# Battery_Manager.net
KiCad netlist of a schematic drawn in Altium Designer
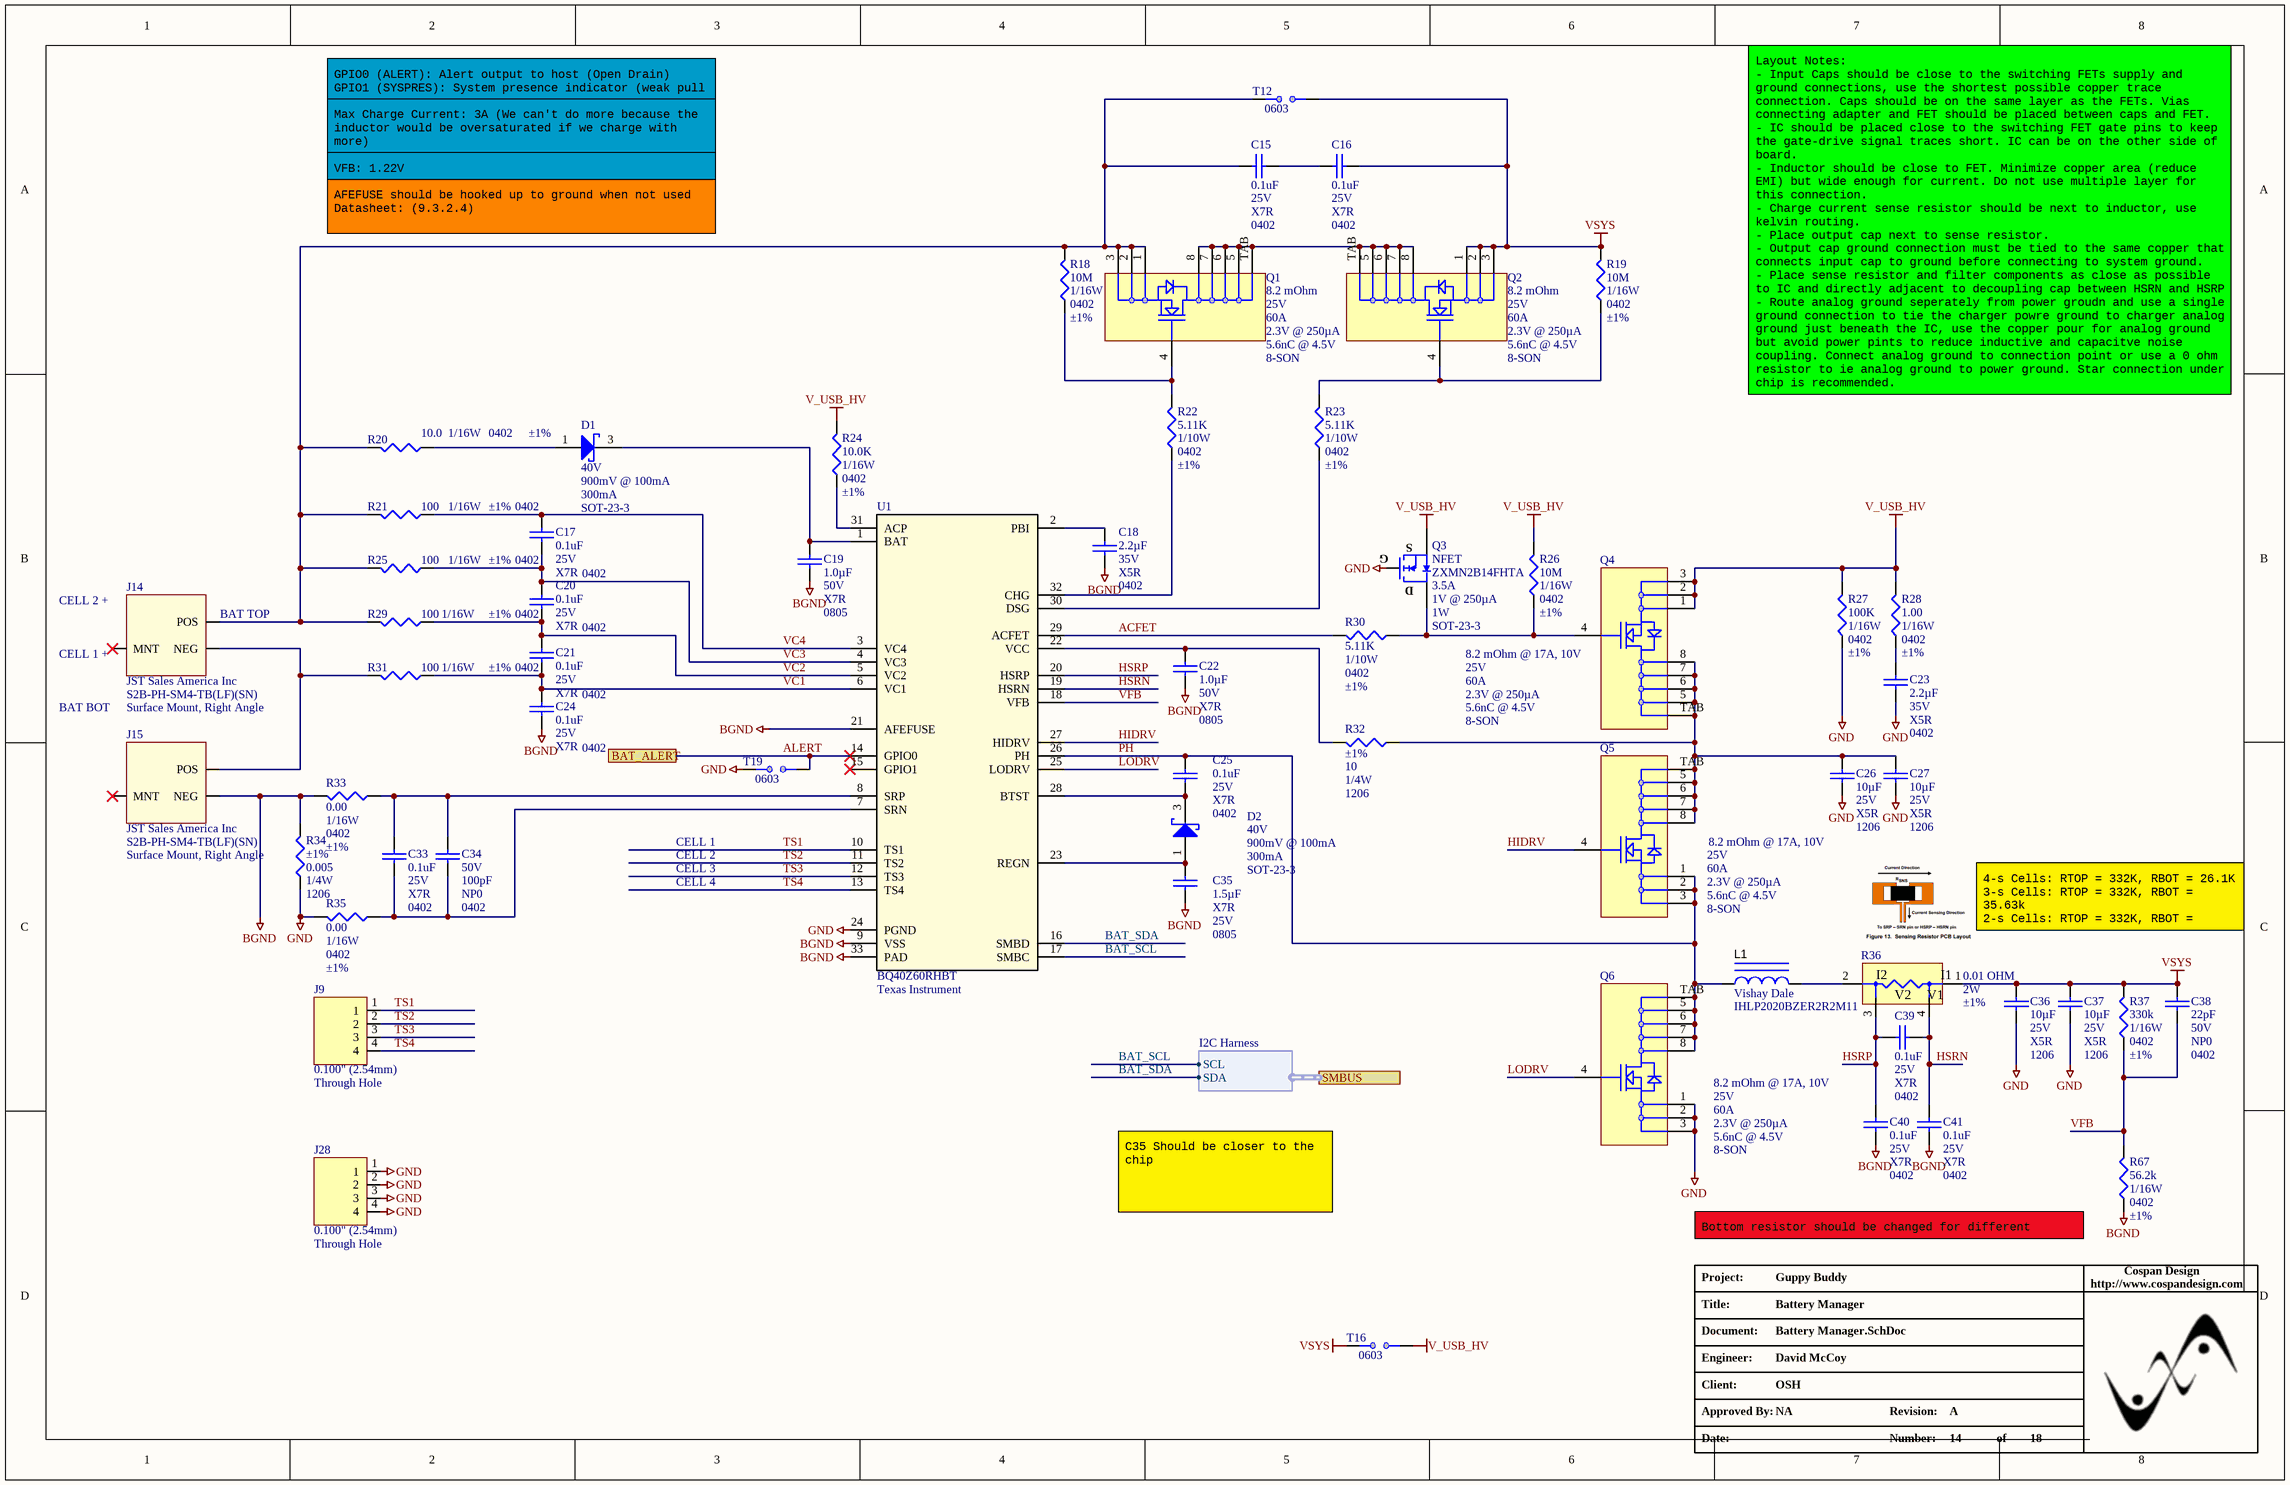
[diagram p0: Battery Manager.SchDoc]

(export (version "E")
  (design (tool "Eeschema 10.0.6"))
  (components
    (comp (ref "C15")
      (value "C_0402_0.1UF_25V")
      (footprint "C_0402")
      (description "CAP CER 0.1UF 25V X6S 0402")
      (fields
        (field (name "TOLERANCE") "10%")
        (field (name "CAPACITANCE") "0.1uF")
        (field (name "VOLTAGE - RATED") "25V")
        (field (name "TEMPERATURE COEFFICIENT") "X7R")
        (field (name "PACKAGE / CASE") "0402")
      )
      (libsource (lib "Cospan Design") (part "C_0402_0.1UF_25V"))
    )
    (comp (ref "C16")
      (value "C_0402_0.1UF_25V")
      (footprint "C_0402")
      (description "CAP CER 0.1UF 25V X6S 0402")
      (fields
        (field (name "TOLERANCE") "10%")
        (field (name "CAPACITANCE") "0.1uF")
        (field (name "VOLTAGE - RATED") "25V")
        (field (name "TEMPERATURE COEFFICIENT") "X7R")
        (field (name "PACKAGE / CASE") "0402")
      )
      (libsource (lib "Cospan Design") (part "C_0402_0.1UF_25V"))
    )
    (comp (ref "C17")
      (value "C_0402_0.1UF_25V")
      (footprint "C_0402")
      (description "CAP CER 0.1UF 25V X6S 0402")
      (fields
        (field (name "TOLERANCE") "10%")
        (field (name "CAPACITANCE") "0.1uF")
        (field (name "VOLTAGE - RATED") "25V")
        (field (name "TEMPERATURE COEFFICIENT") "X7R")
        (field (name "PACKAGE / CASE") "0402")
      )
      (libsource (lib "Cospan Design") (part "C_0402_0.1UF_25V"))
    )
    (comp (ref "C18")
      (value "C_0402_2.2uF_35V")
      (footprint "C_0402")
      (description "CAP CER 2.2UF 35V 20% X5R 0402")
      (fields
        (field (name "MANUFACTURER") "TDK Corporation")
        (field (name "MANUFACTURER PART NUMBER") "C1005X5R1V225K050BC")
        (field (name "CAPACITANCE") "2.2µF")
        (field (name "VOLTAGE - RATED") "35V")
        (field (name "TEMPERATURE COEFFICIENT") "X5R")
        (field (name "PACKAGE / CASE") "0402")
      )
      (libsource (lib "Main LibraryX") (part "C_0402_2.2uF_35V"))
    )
    (comp (ref "C19")
      (value "1.0uF")
      (footprint "C_ERA-0805")
      (description "CAP CER 1UF 50V X7R 0805")
      (fields
        (field (name "TOLERANCE") "10%")
        (field (name "CAPACITANCE") "1.0µF")
        (field (name "VOLTAGE - RATED") "50V")
        (field (name "TEMPERATURE COEFFICIENT") "X7R")
        (field (name "PACKAGE / CASE") "0805")
        (field (name "VOLTAGE") "50V")
      )
      (libsource (lib "Main LibraryX") (part "C_0805_1.0uF_50V"))
    )
    (comp (ref "C20")
      (value "C_0402_0.1UF_25V")
      (footprint "C_0402")
      (description "CAP CER 0.1UF 25V X6S 0402")
      (fields
        (field (name "TOLERANCE") "10%")
        (field (name "CAPACITANCE") "0.1uF")
        (field (name "VOLTAGE - RATED") "25V")
        (field (name "TEMPERATURE COEFFICIENT") "X7R")
        (field (name "PACKAGE / CASE") "0402")
      )
      (libsource (lib "Cospan Design") (part "C_0402_0.1UF_25V"))
    )
    (comp (ref "C21")
      (value "C_0402_0.1UF_25V")
      (footprint "C_0402")
      (description "CAP CER 0.1UF 25V X6S 0402")
      (fields
        (field (name "TOLERANCE") "10%")
        (field (name "CAPACITANCE") "0.1uF")
        (field (name "VOLTAGE - RATED") "25V")
        (field (name "TEMPERATURE COEFFICIENT") "X7R")
        (field (name "PACKAGE / CASE") "0402")
      )
      (libsource (lib "Cospan Design") (part "C_0402_0.1UF_25V"))
    )
    (comp (ref "C22")
      (value "1.0uF")
      (footprint "C_ERA-0805")
      (description "CAP CER 1UF 50V X7R 0805")
      (fields
        (field (name "TOLERANCE") "10%")
        (field (name "CAPACITANCE") "1.0µF")
        (field (name "VOLTAGE - RATED") "50V")
        (field (name "TEMPERATURE COEFFICIENT") "X7R")
        (field (name "PACKAGE / CASE") "0805")
        (field (name "VOLTAGE") "50V")
      )
      (libsource (lib "Main LibraryX") (part "C_0805_1.0uF_50V"))
    )
    (comp (ref "C23")
      (value "C_0402_2.2uF_35V")
      (footprint "C_0402")
      (description "CAP CER 2.2UF 35V 20% X5R 0402")
      (fields
        (field (name "MANUFACTURER") "TDK Corporation")
        (field (name "MANUFACTURER PART NUMBER") "C1005X5R1V225K050BC")
        (field (name "CAPACITANCE") "2.2µF")
        (field (name "VOLTAGE - RATED") "35V")
        (field (name "TEMPERATURE COEFFICIENT") "X5R")
        (field (name "PACKAGE / CASE") "0402")
      )
      (libsource (lib "Main LibraryX") (part "C_0402_2.2uF_35V"))
    )
    (comp (ref "C24")
      (value "C_0402_0.1UF_25V")
      (footprint "C_0402")
      (description "CAP CER 0.1UF 25V X6S 0402")
      (fields
        (field (name "TOLERANCE") "10%")
        (field (name "CAPACITANCE") "0.1uF")
        (field (name "VOLTAGE - RATED") "25V")
        (field (name "TEMPERATURE COEFFICIENT") "X7R")
        (field (name "PACKAGE / CASE") "0402")
      )
      (libsource (lib "Cospan Design") (part "C_0402_0.1UF_25V"))
    )
    (comp (ref "C25")
      (value "C_0402_0.1UF_25V")
      (footprint "C_0402")
      (description "CAP CER 0.1UF 25V X6S 0402")
      (fields
        (field (name "TOLERANCE") "10%")
        (field (name "CAPACITANCE") "0.1uF")
        (field (name "VOLTAGE - RATED") "25V")
        (field (name "TEMPERATURE COEFFICIENT") "X7R")
        (field (name "PACKAGE / CASE") "0402")
      )
      (libsource (lib "Cospan Design") (part "C_0402_0.1UF_25V"))
    )
    (comp (ref "C26")
      (value "10µF")
      (footprint "CAP-1206")
      (description "CAP CER 10UF 25V X5R 1206")
      (fields
        (field (name "TOLERANCE") "10%")
        (field (name "CAPACITANCE") "10µF")
        (field (name "VOLTAGE - RATED") "25V")
        (field (name "TEMPERATURE COEFFICIENT") "X5R")
        (field (name "PACKAGE / CASE") "1206")
        (field (name "VOLTAGE") "25V")
      )
      (libsource (lib "Main LibraryX") (part "C_1206_10UF_25V"))
    )
    (comp (ref "C27")
      (value "10µF")
      (footprint "CAP-1206")
      (description "CAP CER 10UF 25V X5R 1206")
      (fields
        (field (name "TOLERANCE") "10%")
        (field (name "CAPACITANCE") "10µF")
        (field (name "VOLTAGE - RATED") "25V")
        (field (name "TEMPERATURE COEFFICIENT") "X5R")
        (field (name "PACKAGE / CASE") "1206")
        (field (name "VOLTAGE") "25V")
      )
      (libsource (lib "Main LibraryX") (part "C_1206_10UF_25V"))
    )
    (comp (ref "C33")
      (value "C_0402_0.1UF_25V")
      (footprint "C_0402")
      (description "CAP CER 0.1UF 25V X6S 0402")
      (fields
        (field (name "TOLERANCE") "10%")
        (field (name "CAPACITANCE") "0.1uF")
        (field (name "VOLTAGE - RATED") "25V")
        (field (name "TEMPERATURE COEFFICIENT") "X7R")
        (field (name "PACKAGE / CASE") "0402")
      )
      (libsource (lib "Cospan Design") (part "C_0402_0.1UF_25V"))
    )
    (comp (ref "C34")
      (value "100pF")
      (footprint "C_0402")
      (description "CAP CER 100PF 50V 5% C0G 0402")
      (fields
        (field (name "MANUFACTURER") "Murata Electronics North America")
        (field (name "MANUFACTURER PART NUMBER") "GRM1555C1H101JA01D")
        (field (name "VOLTAGE - RATED") "50V")
        (field (name "CAPACITANCE") "100pF")
        (field (name "TEMPERATURE COEFFICIENT") "NP0")
        (field (name "PACKAGE / CASE") "0402")
      )
      (libsource (lib "Main LibraryX") (part "C_0402_100PF"))
    )
    (comp (ref "C35")
      (value "C_0805_1.5uF_25V")
      (footprint "C_ERA-0805")
      (description "1.5µF ±10% 25V Ceramic Capacitor X7R 0805 (2012 Metric)")
      (fields
        (field (name "MANUFACTURER") "Murata Electronics North America")
        (field (name "MANUFACTURER PART NUMBER") "GRM21BR71E155KA88L")
        (field (name "CAPACITANCE") "1.5µF")
        (field (name "VOLTAGE - RATED") "X7R")
        (field (name "TEMPERATURE COEFFICIENT") "25V")
        (field (name "PACKAGE / CASE") "0805")
      )
      (libsource (lib "Cospan Design") (part "C_0805_1.5uF_25V"))
    )
    (comp (ref "C36")
      (value "10µF")
      (footprint "CAP-1206")
      (description "CAP CER 10UF 25V X5R 1206")
      (fields
        (field (name "TOLERANCE") "10%")
        (field (name "CAPACITANCE") "10µF")
        (field (name "VOLTAGE - RATED") "25V")
        (field (name "TEMPERATURE COEFFICIENT") "X5R")
        (field (name "PACKAGE / CASE") "1206")
        (field (name "VOLTAGE") "25V")
      )
      (libsource (lib "Main LibraryX") (part "C_1206_10UF_25V"))
    )
    (comp (ref "C37")
      (value "10µF")
      (footprint "CAP-1206")
      (description "CAP CER 10UF 25V X5R 1206")
      (fields
        (field (name "TOLERANCE") "10%")
        (field (name "CAPACITANCE") "10µF")
        (field (name "VOLTAGE - RATED") "25V")
        (field (name "TEMPERATURE COEFFICIENT") "X5R")
        (field (name "PACKAGE / CASE") "1206")
        (field (name "VOLTAGE") "25V")
      )
      (libsource (lib "Main LibraryX") (part "C_1206_10UF_25V"))
    )
    (comp (ref "C38")
      (value "22pF")
      (footprint "C_0402")
      (description "CAP CER 22PF 50V NP0 0402")
      (fields
        (field (name "MANUFACTURER") "Murata Electronics North America")
        (field (name "MANUFACTURER PART NUMBER") "GRM1555C1H220FA01D")
        (field (name "CAPACITANCE") "22pF")
        (field (name "VOLTAGE - RATED") "50V")
        (field (name "TEMPERATURE COEFFICIENT") "NP0")
        (field (name "PACKAGE / CASE") "0402")
      )
      (libsource (lib "Main LibraryX") (part "C_0402_22PF_50V"))
    )
    (comp (ref "C39")
      (value "C_0402_0.1UF_25V")
      (footprint "C_0402")
      (description "CAP CER 0.1UF 25V X6S 0402")
      (fields
        (field (name "TOLERANCE") "10%")
        (field (name "CAPACITANCE") "0.1uF")
        (field (name "VOLTAGE - RATED") "25V")
        (field (name "TEMPERATURE COEFFICIENT") "X7R")
        (field (name "PACKAGE / CASE") "0402")
      )
      (libsource (lib "Cospan Design") (part "C_0402_0.1UF_25V"))
    )
    (comp (ref "C40")
      (value "C_0402_0.1UF_25V")
      (footprint "C_0402")
      (description "CAP CER 0.1UF 25V X6S 0402")
      (fields
        (field (name "TOLERANCE") "10%")
        (field (name "CAPACITANCE") "0.1uF")
        (field (name "VOLTAGE - RATED") "25V")
        (field (name "TEMPERATURE COEFFICIENT") "X7R")
        (field (name "PACKAGE / CASE") "0402")
      )
      (libsource (lib "Cospan Design") (part "C_0402_0.1UF_25V"))
    )
    (comp (ref "C41")
      (value "C_0402_0.1UF_25V")
      (footprint "C_0402")
      (description "CAP CER 0.1UF 25V X6S 0402")
      (fields
        (field (name "TOLERANCE") "10%")
        (field (name "CAPACITANCE") "0.1uF")
        (field (name "VOLTAGE - RATED") "25V")
        (field (name "TEMPERATURE COEFFICIENT") "X7R")
        (field (name "PACKAGE / CASE") "0402")
      )
      (libsource (lib "Cospan Design") (part "C_0402_0.1UF_25V"))
    )
    (comp (ref "D1")
      (value "BAT54")
      (footprint "SOT23")
      (description "DIODE SCHOTTKY 40V 300MA SOT-23")
      (fields
        (field (name "VOLTAGE - DC REVERSE (VR) (MAX)") "40V")
        (field (name "VOLTAGE - FORWARD (VF) (MAX) @ IF") "900mV @ 100mA")
        (field (name "CURRENT - AVERAGE RECTIFIED (IO)") "300mA")
        (field (name "PACKAGE / CASE") "SOT-23-3")
      )
      (libsource (lib "Main Library") (part "D_SCHOTT_BAT54WFILM"))
    )
    (comp (ref "D2")
      (value "BAT54")
      (footprint "SOT23")
      (description "DIODE SCHOTTKY 40V 300MA SOT-23")
      (fields
        (field (name "VOLTAGE - DC REVERSE (VR) (MAX)") "40V")
        (field (name "VOLTAGE - FORWARD (VF) (MAX) @ IF") "900mV @ 100mA")
        (field (name "CURRENT - AVERAGE RECTIFIED (IO)") "300mA")
        (field (name "PACKAGE / CASE") "SOT-23-3")
      )
      (libsource (lib "Main Library") (part "D_SCHOTT_BAT54WFILM"))
    )
    (comp (ref "J9")
      (value "J_HDR1X4_THRHOLE_VERT")
      (footprint "HDR_1X4")
      (description "CONN HEADER .100\" 4POS TIN PCB")
      (fields
        (field (name "MANUFACTURER") "Samtec")
        (field (name "MANUFACTURER PART NUMBER") "TSW-104-07-T-S")
        (field (name "PITCH") "0.100\" (2.54mm)")
        (field (name "MOUNTING TYPE") "Through Hole")
      )
      (libsource (lib "Main Library") (part "J_HDR1X4_THRHOLE_VERT"))
    )
    (comp (ref "J14")
      (value "J_LIPO_BAT_CONNECTOR")
      (footprint "HDR_1X2_LIPO_BATTERY")
      (description "CONN HEADER PH SIDE 2POS 2MM SMD")
      (fields
        (field (name "MANUFACTURER") "JST Sales America Inc")
        (field (name "MANUFACTURER PART NUMBER") "S2B-PH-SM4-TB(LF)(SN)")
        (field (name "MOUNTING TYPE") "Surface Mount, Right Angle")
      )
      (libsource (lib "Main Library") (part "J_LIPO_BAT_CONNECTOR"))
    )
    (comp (ref "J15")
      (value "J_LIPO_BAT_CONNECTOR")
      (footprint "HDR_1X2_LIPO_BATTERY")
      (description "CONN HEADER PH SIDE 2POS 2MM SMD")
      (fields
        (field (name "MANUFACTURER") "JST Sales America Inc")
        (field (name "MANUFACTURER PART NUMBER") "S2B-PH-SM4-TB(LF)(SN)")
        (field (name "MOUNTING TYPE") "Surface Mount, Right Angle")
      )
      (libsource (lib "Main Library") (part "J_LIPO_BAT_CONNECTOR"))
    )
    (comp (ref "J28")
      (value "J_HDR1X4_THRHOLE_VERT")
      (footprint "HDR_1X4")
      (description "CONN HEADER .100\" 4POS TIN PCB")
      (fields
        (field (name "MANUFACTURER") "Samtec")
        (field (name "MANUFACTURER PART NUMBER") "TSW-104-07-T-S")
        (field (name "PITCH") "0.100\" (2.54mm)")
        (field (name "MOUNTING TYPE") "Through Hole")
      )
      (libsource (lib "Main Library") (part "J_HDR1X4_THRHOLE_VERT"))
    )
    (comp (ref "L1")
      (value "L_IHLP2020BZER2R2M11")
      (footprint "IHLP-2020BZ")
      (description "2.2µH Shielded Molded Inductor 5A 37.7 mOhm Max")
      (fields
        (field (name "TOLERANCE") "±20%")
        (field (name "MANUFACTURER") "Vishay Dale")
        (field (name "MANUFACTURER PART NUMBER") "IHLP2020BZER2R2M11")
      )
      (libsource (lib "Cospan Design") (part "L_IHLP2020BZER2R2M11"))
    )
    (comp (ref "Q1")
      (value "N-Channel Nex_FET")
      (footprint "Q_TDSON-8 NexFET")
      (description "MOSFET N-CH 25V 60A 8-SON")
      (fields
        (field (name "MANUFACTURER") "Texas Instruments")
        (field (name "MANUFACTURER PART NUMBER") "CSD16409Q3")
        (field (name "RDS ON (MAX) @ ID, VGS") "8.2 mOhm")
        (field (name "DRAIN TO SOURCE VOLTAGE (VDSS)") "25V")
        (field (name "CURRENT - CONTINUOUS DRAIN (ID) @ 25° C") "60A")
        (field (name "VGS(TH) (MAX) @ ID") "2.3V @ 250µA")
        (field (name "GATE CHARGE (QG) @ VGS") "5.6nC @ 4.5V")
        (field (name "PACKAGE / CASE") "8-SON")
      )
      (libsource (lib "Main Library") (part "Q_N-CH_8SON_60A_9.5mOHM"))
    )
    (comp (ref "Q2")
      (value "N-Channel Nex_FET")
      (footprint "Q_TDSON-8 NexFET")
      (description "MOSFET N-CH 25V 60A 8-SON")
      (fields
        (field (name "MANUFACTURER") "Texas Instruments")
        (field (name "MANUFACTURER PART NUMBER") "CSD16409Q3")
        (field (name "RDS ON (MAX) @ ID, VGS") "8.2 mOhm")
        (field (name "DRAIN TO SOURCE VOLTAGE (VDSS)") "25V")
        (field (name "CURRENT - CONTINUOUS DRAIN (ID) @ 25° C") "60A")
        (field (name "VGS(TH) (MAX) @ ID") "2.3V @ 250µA")
        (field (name "GATE CHARGE (QG) @ VGS") "5.6nC @ 4.5V")
        (field (name "PACKAGE / CASE") "8-SON")
      )
      (libsource (lib "Main Library") (part "Q_N-CH_8SON_60A_9.5mOHM"))
    )
    (comp (ref "Q3")
      (value "NFET")
      (footprint "SOT-23A")
      (description "MOSFET N-CH 20V 3.5A SOT23-3")
      (fields
        (field (name "MANUFACTURER") "Diodes/Zetex")
        (field (name "MANUFACTURER PART NUMBER") "ZXMN2B14FHTA")
        (field (name "CURRENT - CONTINUOUS DRAIN (ID) @ 25° C") "3.5A")
        (field (name "VGS(TH) (MAX) @ ID") "1V @ 250µA")
        (field (name "POWER - MAX") "1W")
        (field (name "PACKAGE / CASE") "SOT-23-3")
      )
      (libsource (lib "Main LibraryX") (part "Q_NFET_3.50A_SOT23"))
    )
    (comp (ref "Q4")
      (value "N-Channel Nex_FET")
      (footprint "Q_TDSON-8 NexFET")
      (description "MOSFET N-CH 25V 60A 8-SON")
      (fields
        (field (name "MANUFACTURER") "Texas Instruments")
        (field (name "MANUFACTURER PART NUMBER") "CSD16409Q3")
        (field (name "RDS ON (MAX) @ ID, VGS") "8.2 mOhm @ 17A, 10V")
        (field (name "DRAIN TO SOURCE VOLTAGE (VDSS)") "25V")
        (field (name "CURRENT - CONTINUOUS DRAIN (ID) @ 25° C") "60A")
        (field (name "VGS(TH) (MAX) @ ID") "2.3V @ 250µA")
        (field (name "GATE CHARGE (QG) @ VGS") "5.6nC @ 4.5V")
        (field (name "PACKAGE / CASE") "8-SON")
      )
      (libsource (lib "Main Library") (part "Q_N-CH_8SON_60A_9.5mOHM"))
    )
    (comp (ref "Q5")
      (value "N-Channel Nex_FET")
      (footprint "Q_TDSON-8 NexFET")
      (description "MOSFET N-CH 25V 60A 8-SON")
      (fields
        (field (name "MANUFACTURER") "Texas Instruments")
        (field (name "MANUFACTURER PART NUMBER") "CSD16409Q3")
        (field (name "RDS ON (MAX) @ ID, VGS") "8.2 mOhm @ 17A, 10V")
        (field (name "DRAIN TO SOURCE VOLTAGE (VDSS)") "25V")
        (field (name "CURRENT - CONTINUOUS DRAIN (ID) @ 25° C") "60A")
        (field (name "VGS(TH) (MAX) @ ID") "2.3V @ 250µA")
        (field (name "GATE CHARGE (QG) @ VGS") "5.6nC @ 4.5V")
        (field (name "PACKAGE / CASE") "8-SON")
      )
      (libsource (lib "Main Library") (part "Q_N-CH_8SON_60A_9.5mOHM"))
    )
    (comp (ref "Q6")
      (value "N-Channel Nex_FET")
      (footprint "Q_TDSON-8 NexFET")
      (description "MOSFET N-CH 25V 60A 8-SON")
      (fields
        (field (name "MANUFACTURER") "Texas Instruments")
        (field (name "MANUFACTURER PART NUMBER") "CSD16409Q3")
        (field (name "RDS ON (MAX) @ ID, VGS") "8.2 mOhm @ 17A, 10V")
        (field (name "DRAIN TO SOURCE VOLTAGE (VDSS)") "25V")
        (field (name "CURRENT - CONTINUOUS DRAIN (ID) @ 25° C") "60A")
        (field (name "VGS(TH) (MAX) @ ID") "2.3V @ 250µA")
        (field (name "GATE CHARGE (QG) @ VGS") "5.6nC @ 4.5V")
        (field (name "PACKAGE / CASE") "8-SON")
      )
      (libsource (lib "Main Library") (part "Q_N-CH_8SON_60A_9.5mOHM"))
    )
    (comp (ref "R18")
      (value "R_0402_10M")
      (footprint "R_0402")
      (description "RES SMD 10M OHM 1% 1/16W 0402")
      (fields
        (field (name "MANUFACTURER") "Yageo")
        (field (name "MANUFACTURER PART NUMBER") "RC0402FR-0710ML")
        (field (name "RESISTANCE IN OHMS") "10M")
        (field (name "POWER (WATTS)") "1/16W")
        (field (name "CASE") "0402")
        (field (name "TOLERANCE") "±1%")
      )
      (libsource (lib "Cospan Design") (part "R_0402_10M"))
    )
    (comp (ref "R19")
      (value "R_0402_10M")
      (footprint "R_0402")
      (description "RES SMD 10M OHM 1% 1/16W 0402")
      (fields
        (field (name "MANUFACTURER") "Yageo")
        (field (name "MANUFACTURER PART NUMBER") "RC0402FR-0710ML")
        (field (name "RESISTANCE IN OHMS") "10M")
        (field (name "POWER (WATTS)") "1/16W")
        (field (name "CASE") "0402")
        (field (name "TOLERANCE") "±1%")
      )
      (libsource (lib "Cospan Design") (part "R_0402_10M"))
    )
    (comp (ref "R20")
      (value "R_0402_10.0")
      (footprint "R_0402")
      (description "RES 10.0 OHM 1/16W 1% 0402 SMD")
      (fields
        (field (name "MANUFACTURER") "Yageo")
        (field (name "MANUFACTURER PART NUMBER") "RC0402FR-0710RL")
        (field (name "RESISTANCE IN OHMS") "10.0")
        (field (name "POWER (WATTS)") "1/16W")
        (field (name "CASE") "0402")
        (field (name "TOLERANCE") "±1%")
      )
      (libsource (lib "Main LibraryX") (part "R_0402_10.0"))
    )
    (comp (ref "R21")
      (value "R_0402_100.0")
      (footprint "R_0402")
      (description "RES 100 OHM 1/16W 1% 0402 SMD")
      (fields
        (field (name "MANUFACTURER") "Yageo")
        (field (name "MANUFACTURER PART NUMBER") "RC0402FR-07100RL")
        (field (name "CASE") "0402")
        (field (name "RESISTANCE IN OHMS") "100")
        (field (name "POWER (WATTS)") "1/16W")
        (field (name "TOLERANCE") "±1%")
      )
      (libsource (lib "Main LibraryX") (part "R_0402_100.0"))
    )
    (comp (ref "R22")
      (value "5.11k Ohms")
      (footprint "R_0402")
      (description "RES 5.11K OHM 1/10W 1% 0402 SMD")
      (fields
        (field (name "MANUFACTURER") "Panasonic - ECG")
        (field (name "MANUFACTURER PART NUMBER") "ERJ-2RKF5111X")
        (field (name "RESISTANCE IN OHMS") "5.11K")
        (field (name "POWER (WATTS)") "1/10W")
        (field (name "CASE") "0402")
        (field (name "TOLERANCE") "±1%")
      )
      (libsource (lib "Main Library") (part "R_0402_5.11K"))
    )
    (comp (ref "R23")
      (value "5.11k Ohms")
      (footprint "R_0402")
      (description "RES 5.11K OHM 1/10W 1% 0402 SMD")
      (fields
        (field (name "MANUFACTURER") "Panasonic - ECG")
        (field (name "MANUFACTURER PART NUMBER") "ERJ-2RKF5111X")
        (field (name "RESISTANCE IN OHMS") "5.11K")
        (field (name "POWER (WATTS)") "1/10W")
        (field (name "CASE") "0402")
        (field (name "TOLERANCE") "±1%")
      )
      (libsource (lib "Main Library") (part "R_0402_5.11K"))
    )
    (comp (ref "R24")
      (value "R_0402_10.0K")
      (footprint "R_0402")
      (description "RES 10.0K OHM 1/16W 1% 0402 SMD")
      (fields
        (field (name "MANUFACTURER") "Stackpole Electronics Inc")
        (field (name "MANUFACTURER PART NUMBER") "RMCF0402FT10K0")
        (field (name "RESISTANCE IN OHMS") "10.0K")
        (field (name "POWER (WATTS)") "1/16W")
        (field (name "CASE") "0402")
        (field (name "TOLERANCE") "±1%")
      )
      (libsource (lib "Main Library") (part "R_0402_10.0K"))
    )
    (comp (ref "R25")
      (value "R_0402_100.0")
      (footprint "R_0402")
      (description "RES 100 OHM 1/16W 1% 0402 SMD")
      (fields
        (field (name "MANUFACTURER") "Yageo")
        (field (name "MANUFACTURER PART NUMBER") "RC0402FR-07100RL")
        (field (name "CASE") "0402")
        (field (name "RESISTANCE IN OHMS") "100")
        (field (name "POWER (WATTS)") "1/16W")
        (field (name "TOLERANCE") "±1%")
      )
      (libsource (lib "Main LibraryX") (part "R_0402_100.0"))
    )
    (comp (ref "R26")
      (value "R_0402_10M")
      (footprint "R_0402")
      (description "RES SMD 10M OHM 1% 1/16W 0402")
      (fields
        (field (name "MANUFACTURER") "Yageo")
        (field (name "MANUFACTURER PART NUMBER") "RC0402FR-0710ML")
        (field (name "RESISTANCE IN OHMS") "10M")
        (field (name "POWER (WATTS)") "1/16W")
        (field (name "CASE") "0402")
        (field (name "TOLERANCE") "±1%")
      )
      (libsource (lib "Cospan Design") (part "R_0402_10M"))
    )
    (comp (ref "R27")
      (value "R_0402_100.0K")
      (footprint "R_0402")
      (description "RES 100K OHM 1/16W 1% 0402 SMD")
      (fields
        (field (name "MANUFACTURER") "Stackpole Electronics Inc")
        (field (name "MANUFACTURER PART NUMBER") "RMCF0402FT100K")
        (field (name "RESISTANCE IN OHMS") "100K")
        (field (name "POWER (WATTS)") "1/16W")
        (field (name "CASE") "0402")
        (field (name "TOLERANCE") "±1%")
      )
      (libsource (lib "Main Library") (part "R_0402_100.0K"))
    )
    (comp (ref "R28")
      (value "1.0 Ohms")
      (footprint "R_0402")
      (description "RES 1.00 OHM 1/16W 1% 0402 SMD")
      (fields
        (field (name "MANUFACTURER") "Yageo")
        (field (name "MANUFACTURER PART NUMBER") "RC0402FR-071RL")
        (field (name "RESISTANCE IN OHMS") "1.00")
        (field (name "POWER (WATTS)") "1/16W")
        (field (name "CASE") "0402")
        (field (name "TOLERANCE") "±1%")
      )
      (libsource (lib "Main Library") (part "R_0402_1.00"))
    )
    (comp (ref "R29")
      (value "R_0402_100.0")
      (footprint "R_0402")
      (description "RES 100 OHM 1/16W 1% 0402 SMD")
      (fields
        (field (name "MANUFACTURER") "Yageo")
        (field (name "MANUFACTURER PART NUMBER") "RC0402FR-07100RL")
        (field (name "CASE") "0402")
        (field (name "RESISTANCE IN OHMS") "100")
        (field (name "POWER (WATTS)") "1/16W")
        (field (name "TOLERANCE") "±1%")
      )
      (libsource (lib "Main LibraryX") (part "R_0402_100.0"))
    )
    (comp (ref "R30")
      (value "5.11k Ohms")
      (footprint "R_0402")
      (description "RES 5.11K OHM 1/10W 1% 0402 SMD")
      (fields
        (field (name "MANUFACTURER") "Panasonic - ECG")
        (field (name "MANUFACTURER PART NUMBER") "ERJ-2RKF5111X")
        (field (name "RESISTANCE IN OHMS") "5.11K")
        (field (name "POWER (WATTS)") "1/10W")
        (field (name "CASE") "0402")
        (field (name "TOLERANCE") "±1%")
      )
      (libsource (lib "Main Library") (part "R_0402_5.11K"))
    )
    (comp (ref "R31")
      (value "R_0402_100.0")
      (footprint "R_0402")
      (description "RES 100 OHM 1/16W 1% 0402 SMD")
      (fields
        (field (name "MANUFACTURER") "Yageo")
        (field (name "MANUFACTURER PART NUMBER") "RC0402FR-07100RL")
        (field (name "CASE") "0402")
        (field (name "RESISTANCE IN OHMS") "100")
        (field (name "POWER (WATTS)") "1/16W")
        (field (name "TOLERANCE") "±1%")
      )
      (libsource (lib "Main LibraryX") (part "R_0402_100.0"))
    )
    (comp (ref "R32")
      (value "R_1206_10")
      (footprint "R_1206")
      (description "RES SMD 10 OHM 1% 1/4W 1206")
      (fields
        (field (name "MANUFACTURER") "Yageo")
        (field (name "MANUFACTURER PART NUMBER") "RC1206FR-0710RL")
        (field (name "TOLERANCE") "±1%")
        (field (name "RESISTANCE IN OHMS") "10")
        (field (name "POWER (WATTS)") "1/4W")
        (field (name "CASE") "1206")
      )
      (libsource (lib "Cospan Design") (part "R_1206_10"))
    )
    (comp (ref "R33")
      (value "0.0 Ohms")
      (footprint "R_0402")
      (description "RES 0.00 OHM 1/16W 1% 0402 SMD")
      (fields
        (field (name "MANUFACTURER") "Yageo")
        (field (name "MANUFACTURER PART NUMBER") "RC0402JR-070RL")
        (field (name "RESISTANCE IN OHMS") "0.00")
        (field (name "POWER (WATTS)") "1/16W")
        (field (name "CASE") "0402")
        (field (name "TOLERANCE") "±1%")
      )
      (libsource (lib "Cospan Design") (part "R_0402_0.00"))
    )
    (comp (ref "R34")
      (value "R_1206_0.005")
      (footprint "R_1206")
      (description "RES SMD 0.005 OHM 1% 1W 1206")
      (fields
        (field (name "MANUFACTURER") "Stackpole Electronics Inc.")
        (field (name "MANUFACTURER PART NUMBER") "CSRF1206FT5L00")
        (field (name "TOLERANCE") "±1%")
        (field (name "RESISTANCE IN OHMS") "0.005")
        (field (name "POWER (WATTS)") "1/4W")
        (field (name "CASE") "1206")
      )
      (libsource (lib "Cospan Design") (part "R_1206_0.005"))
    )
    (comp (ref "R35")
      (value "0.0 Ohms")
      (footprint "R_0402")
      (description "RES 0.00 OHM 1/16W 1% 0402 SMD")
      (fields
        (field (name "MANUFACTURER") "Yageo")
        (field (name "MANUFACTURER PART NUMBER") "RC0402JR-070RL")
        (field (name "RESISTANCE IN OHMS") "0.00")
        (field (name "POWER (WATTS)") "1/16W")
        (field (name "CASE") "0402")
        (field (name "TOLERANCE") "±1%")
      )
      (libsource (lib "Cospan Design") (part "R_0402_0.00"))
    )
    (comp (ref "R36")
      (value "0.01 OHM")
      (footprint "R_LVK25_0.003")
      (description "RES SMD 0.01 OHM 1% 2W 1224")
      (fields
        (field (name "MANUFACTURER") "Ohmite")
        (field (name "MANUFACTURER PART NUMBER") "LVK25R010FER")
        (field (name "POWER (WATTS)") "2W")
        (field (name "TOLERANCE") "±1%")
      )
      (libsource (lib "Main Library") (part "R_0.010SENSE_LK20"))
    )
    (comp (ref "R37")
      (value "R_0402_330K")
      (footprint "R_0402")
      (description "RES SMD 330K OHM 1% 1/16W 0402")
      (fields
        (field (name "MANUFACTURER") "Yageo")
        (field (name "MANUFACTURER PART NUMBER") "RC0402FR-07330KL")
        (field (name "RESISTANCE IN OHMS") "330k")
        (field (name "POWER (WATTS)") "1/16W")
        (field (name "CASE") "0402")
        (field (name "TOLERANCE") "±1%")
      )
      (libsource (lib "Cospan Design") (part "R_0402_330K"))
    )
    (comp (ref "R67")
      (value "56.2k")
      (footprint "R_0402")
      (description "RES 56.2K OHM 1/16W 1% 0402 SMD")
      (fields
        (field (name "MANUFACTURER") "Vishay Dale")
        (field (name "MANUFACTURER PART NUMBER") "CRCW040256K2FKED")
        (field (name "RESISTANCE IN OHMS") "56.2k")
        (field (name "POWER (WATTS)") "1/16W")
        (field (name "CASE") "0402")
        (field (name "TOLERANCE") "±1%")
      )
      (libsource (lib "Main Library") (part "R_0402_56.2k"))
    )
    (comp (ref "T12")
      (value "Place Solder Bridge to Enable")
      (footprint "ERA-0603-SOLDER_JUMPER")
      (description "SOLDER_JUMPER PAD")
      (fields (field (name "CASE") "0603"))
      (libsource (lib "Main Library") (part "T_0603_JUMPER_PAD"))
    )
    (comp (ref "T16")
      (value "Place Solder Bridge to Enable")
      (footprint "ERA-0603-SOLDER_JUMPER")
      (description "SOLDER_JUMPER PAD")
      (fields (field (name "CASE") "0603"))
      (libsource (lib "Main Library") (part "T_0603_JUMPER_PAD"))
    )
    (comp (ref "T19")
      (value "Place Solder Bridge to Enable")
      (footprint "ERA-0603-SOLDER_JUMPER")
      (description "SOLDER_JUMPER PAD")
      (fields (field (name "CASE") "0603"))
      (libsource (lib "Main Library") (part "T_0603_JUMPER_PAD"))
    )
    (comp (ref "U1")
      (value "U_BQ40Z60RHBR")
      (footprint "RHB0032E")
      (description "IC BATTERY MANAGER 32VQFN")
      (fields
        (field (name "MANUFACTURER PART NUMBER") "BQ40Z60RHBT")
        (field (name "MANUFACTURER") "Texas Instrument")
      )
      (libsource (lib "Cospan Design") (part "U_BQ40Z60RHBR"))
    )
  )
  (nets
    (net (code "3") (name "/ACFET") (class "Default")
      (node (ref "R30") (pin "1") (pinfunction "1_1") (pintype "passive"))
      (node (ref "U1") (pin "29") (pinfunction "ACFET_29") (pintype "passive"))
    )
    (net (code "4") (name "/ALERT") (class "Default")
      (node (ref "T19") (pin "1") (pinfunction "1_1") (pintype "passive"))
      (node (ref "U1") (pin "14") (pinfunction "GPIO0_14") (pintype "passive"))
    )
    (net (code "5") (name "/BAT_SCL") (class "Default")
      (node (ref "U1") (pin "17") (pinfunction "SMBC_17") (pintype "passive"))
    )
    (net (code "6") (name "/BAT_SDA") (class "Default")
      (node (ref "U1") (pin "16") (pinfunction "SMBD_16") (pintype "passive"))
    )
    (net (code "7") (name "/HIDRV") (class "Default")
      (node (ref "Q5") (pin "4") (pinfunction "G1_4") (pintype "passive"))
      (node (ref "U1") (pin "27") (pinfunction "HIDRV_27") (pintype "passive"))
    )
    (net (code "8") (name "/HSRN") (class "Default")
      (node (ref "C39") (pin "1") (pinfunction "1_1") (pintype "passive"))
      (node (ref "C41") (pin "1") (pinfunction "1_1") (pintype "passive"))
      (node (ref "R36") (pin "4") (pinfunction "V1_4") (pintype "passive"))
      (node (ref "U1") (pin "19") (pinfunction "HSRN_19") (pintype "passive"))
    )
    (net (code "9") (name "/HSRP") (class "Default")
      (node (ref "C39") (pin "2") (pinfunction "2_2") (pintype "passive"))
      (node (ref "C40") (pin "1") (pinfunction "1_1") (pintype "passive"))
      (node (ref "R36") (pin "3") (pinfunction "V2_3") (pintype "passive"))
      (node (ref "U1") (pin "20") (pinfunction "HSRP_20") (pintype "passive"))
    )
    (net (code "10") (name "/LODRV") (class "Default")
      (node (ref "Q6") (pin "4") (pinfunction "G1_4") (pintype "passive"))
      (node (ref "U1") (pin "25") (pinfunction "LODRV_25") (pintype "passive"))
    )
    (net (code "11") (name "/PH") (class "Default")
      (node (ref "C25") (pin "1") (pinfunction "1_1") (pintype "passive"))
      (node (ref "L1") (pin "2") (pinfunction "2_2") (pintype "passive"))
      (node (ref "Q5") (pin "1") (pinfunction "S1_1") (pintype "passive"))
      (node (ref "Q5") (pin "2") (pintype "passive"))
      (node (ref "Q5") (pin "3") (pintype "passive"))
      (node (ref "Q6") (pin "5") (pintype "passive"))
      (node (ref "Q6") (pin "6") (pintype "passive"))
      (node (ref "Q6") (pin "7") (pinfunction "D2a_7") (pintype "passive"))
      (node (ref "Q6") (pin "8") (pinfunction "D2b_8") (pintype "passive"))
      (node (ref "Q6") (pin "TAB") (pintype "passive"))
      (node (ref "U1") (pin "26") (pinfunction "PH_26") (pintype "passive"))
    )
    (net (code "12") (name "/TS1") (class "Default")
      (node (ref "J9") (pin "1") (pinfunction "1_1") (pintype "passive"))
      (node (ref "U1") (pin "10") (pinfunction "TS1_10") (pintype "passive"))
    )
    (net (code "13") (name "/TS2") (class "Default")
      (node (ref "J9") (pin "2") (pinfunction "2_2") (pintype "passive"))
      (node (ref "U1") (pin "11") (pinfunction "TS2_11") (pintype "passive"))
    )
    (net (code "14") (name "/TS3") (class "Default")
      (node (ref "J9") (pin "3") (pinfunction "3_3") (pintype "passive"))
      (node (ref "U1") (pin "12") (pinfunction "TS3_12") (pintype "passive"))
    )
    (net (code "15") (name "/TS4") (class "Default")
      (node (ref "J9") (pin "4") (pinfunction "4_4") (pintype "passive"))
      (node (ref "U1") (pin "13") (pinfunction "TS4_13") (pintype "passive"))
    )
    (net (code "16") (name "/VC1") (class "Default")
      (node (ref "C21") (pin "1") (pinfunction "1_1") (pintype "passive"))
      (node (ref "C24") (pin "2") (pinfunction "2_2") (pintype "passive"))
      (node (ref "R31") (pin "2") (pinfunction "2_2") (pintype "passive"))
      (node (ref "U1") (pin "6") (pinfunction "VC1_6") (pintype "passive"))
    )
    (net (code "17") (name "/VC2") (class "Default")
      (node (ref "C20") (pin "1") (pinfunction "1_1") (pintype "passive"))
      (node (ref "C21") (pin "2") (pinfunction "2_2") (pintype "passive"))
      (node (ref "R29") (pin "2") (pinfunction "2_2") (pintype "passive"))
      (node (ref "U1") (pin "5") (pinfunction "VC2_5") (pintype "passive"))
    )
    (net (code "18") (name "/VC3") (class "Default")
      (node (ref "C17") (pin "1") (pinfunction "1_1") (pintype "passive"))
      (node (ref "C20") (pin "2") (pinfunction "2_2") (pintype "passive"))
      (node (ref "R25") (pin "2") (pinfunction "2_2") (pintype "passive"))
      (node (ref "U1") (pin "4") (pinfunction "VC3_4") (pintype "passive"))
    )
    (net (code "19") (name "/VC4") (class "Default")
      (node (ref "C17") (pin "2") (pinfunction "2_2") (pintype "passive"))
      (node (ref "R21") (pin "2") (pinfunction "2_2") (pintype "passive"))
      (node (ref "U1") (pin "3") (pinfunction "VC4_3") (pintype "passive"))
    )
    (net (code "20") (name "/VFB") (class "Default")
      (node (ref "C38") (pin "1") (pinfunction "1_1") (pintype "passive"))
      (node (ref "R37") (pin "2") (pinfunction "2_2") (pintype "passive"))
      (node (ref "R67") (pin "1") (pinfunction "1_1") (pintype "passive"))
      (node (ref "U1") (pin "18") (pinfunction "VFB_18") (pintype "passive"))
    )
    (net (code "22") (name "BGND") (class "Default")
      (node (ref "C18") (pin "1") (pinfunction "1_1") (pintype "passive"))
      (node (ref "C19") (pin "1") (pinfunction "1_1") (pintype "passive"))
      (node (ref "C22") (pin "1") (pinfunction "1_1") (pintype "passive"))
      (node (ref "C24") (pin "1") (pinfunction "1_1") (pintype "passive"))
      (node (ref "C35") (pin "1") (pinfunction "1_1") (pintype "passive"))
      (node (ref "C40") (pin "2") (pinfunction "2_2") (pintype "passive"))
      (node (ref "C41") (pin "2") (pinfunction "2_2") (pintype "passive"))
      (node (ref "J15") (pin "2") (pinfunction "NEG_2") (pintype "passive"))
      (node (ref "R33") (pin "1") (pinfunction "1_1") (pintype "passive"))
      (node (ref "R34") (pin "1") (pinfunction "1_1") (pintype "passive"))
      (node (ref "R67") (pin "2") (pinfunction "2_2") (pintype "passive"))
      (node (ref "U1") (pin "21") (pinfunction "AFEFUSE_21") (pintype "passive"))
      (node (ref "U1") (pin "33") (pinfunction "PAD_33") (pintype "passive"))
      (node (ref "U1") (pin "9") (pinfunction "VSS_9") (pintype "passive"))
    )
    (net (code "23") (name "GND") (class "Default")
      (node (ref "C23") (pin "1") (pinfunction "1_1") (pintype "passive"))
      (node (ref "C26") (pin "1") (pinfunction "1_1") (pintype "passive"))
      (node (ref "C27") (pin "1") (pinfunction "1_1") (pintype "passive"))
      (node (ref "C36") (pin "2") (pinfunction "2_2") (pintype "passive"))
      (node (ref "C37") (pin "2") (pinfunction "2_2") (pintype "passive"))
      (node (ref "J28") (pin "1") (pinfunction "1_1") (pintype "passive"))
      (node (ref "J28") (pin "2") (pinfunction "2_2") (pintype "passive"))
      (node (ref "J28") (pin "3") (pinfunction "3_3") (pintype "passive"))
      (node (ref "J28") (pin "4") (pinfunction "4_4") (pintype "passive"))
      (node (ref "Q3") (pin "1") (pinfunction "G_1") (pintype "passive"))
      (node (ref "Q6") (pin "1") (pinfunction "S1_1") (pintype "passive"))
      (node (ref "Q6") (pin "2") (pintype "passive"))
      (node (ref "Q6") (pin "3") (pintype "passive"))
      (node (ref "R27") (pin "2") (pinfunction "2_2") (pintype "passive"))
      (node (ref "R34") (pin "2") (pinfunction "2_2") (pintype "passive"))
      (node (ref "R35") (pin "1") (pinfunction "1_1") (pintype "passive"))
      (node (ref "T19") (pin "2") (pinfunction "2_2") (pintype "passive"))
      (node (ref "U1") (pin "24") (pinfunction "PGND_24") (pintype "passive"))
    )
    (net (code "24") (name "Net-(C15-Pad1)") (class "Default")
      (node (ref "C15") (pin "1") (pinfunction "1_1") (pintype "passive"))
      (node (ref "C16") (pin "2") (pinfunction "2_2") (pintype "passive"))
    )
    (net (code "25") (name "Net-(C23-Pad2)") (class "Default")
      (node (ref "C23") (pin "2") (pinfunction "2_2") (pintype "passive"))
      (node (ref "R28") (pin "2") (pinfunction "2_2") (pintype "passive"))
    )
    (net (code "26") (name "Net-(D1-A)") (class "Default")
      (node (ref "D1") (pin "1") (pinfunction "A_1") (pintype "passive"))
      (node (ref "R20") (pin "2") (pinfunction "2_2") (pintype "passive"))
    )
    (net (code "27") (name "Net-(D1-K)") (class "Default")
      (node (ref "C19") (pin "2") (pinfunction "2_2") (pintype "passive"))
      (node (ref "D1") (pin "3") (pinfunction "K_3") (pintype "passive"))
      (node (ref "U1") (pin "1") (pinfunction "BAT_1") (pintype "passive"))
    )
    (net (code "28") (name "Net-(D2-A)") (class "Default")
      (node (ref "C35") (pin "2") (pinfunction "2_2") (pintype "passive"))
      (node (ref "D2") (pin "1") (pinfunction "A_1") (pintype "passive"))
      (node (ref "U1") (pin "23") (pinfunction "REGN_23") (pintype "passive"))
    )
    (net (code "29") (name "Net-(D2-K)") (class "Default")
      (node (ref "C25") (pin "2") (pinfunction "2_2") (pintype "passive"))
      (node (ref "D2") (pin "3") (pinfunction "K_3") (pintype "passive"))
      (node (ref "U1") (pin "28") (pinfunction "BTST_28") (pintype "passive"))
    )
    (net (code "30") (name "Net-(J14-NEG)") (class "Default")
      (node (ref "J14") (pin "2") (pinfunction "NEG_2") (pintype "passive"))
      (node (ref "J15") (pin "1") (pinfunction "POS_1") (pintype "passive"))
      (node (ref "R31") (pin "1") (pinfunction "1_1") (pintype "passive"))
    )
    (net (code "31") (name "Net-(J14-POS)") (class "Default")
      (node (ref "C15") (pin "2") (pinfunction "2_2") (pintype "passive"))
      (node (ref "J14") (pin "1") (pinfunction "POS_1") (pintype "passive"))
      (node (ref "Q1") (pin "1") (pinfunction "S1_1") (pintype "passive"))
      (node (ref "Q1") (pin "2") (pintype "passive"))
      (node (ref "Q1") (pin "3") (pintype "passive"))
      (node (ref "R18") (pin "1") (pinfunction "1_1") (pintype "passive"))
      (node (ref "R20") (pin "1") (pinfunction "1_1") (pintype "passive"))
      (node (ref "R21") (pin "1") (pinfunction "1_1") (pintype "passive"))
      (node (ref "R25") (pin "1") (pinfunction "1_1") (pintype "passive"))
      (node (ref "R29") (pin "1") (pinfunction "1_1") (pintype "passive"))
      (node (ref "T12") (pin "2") (pinfunction "2_2") (pintype "passive"))
    )
    (net (code "32") (name "Net-(Q1-D2a)") (class "Default")
      (node (ref "Q1") (pin "5") (pintype "passive"))
      (node (ref "Q1") (pin "6") (pintype "passive"))
      (node (ref "Q1") (pin "7") (pinfunction "D2a_7") (pintype "passive"))
      (node (ref "Q1") (pin "8") (pinfunction "D2b_8") (pintype "passive"))
      (node (ref "Q1") (pin "TAB") (pintype "passive"))
      (node (ref "Q2") (pin "5") (pintype "passive"))
      (node (ref "Q2") (pin "6") (pintype "passive"))
      (node (ref "Q2") (pin "7") (pinfunction "D2a_7") (pintype "passive"))
      (node (ref "Q2") (pin "8") (pinfunction "D2b_8") (pintype "passive"))
      (node (ref "Q2") (pin "TAB") (pintype "passive"))
    )
    (net (code "33") (name "Net-(Q1-G1)") (class "Default")
      (node (ref "Q1") (pin "4") (pinfunction "G1_4") (pintype "passive"))
      (node (ref "R18") (pin "2") (pinfunction "2_2") (pintype "passive"))
      (node (ref "R22") (pin "1") (pinfunction "1_1") (pintype "passive"))
    )
    (net (code "34") (name "Net-(Q2-G1)") (class "Default")
      (node (ref "Q2") (pin "4") (pinfunction "G1_4") (pintype "passive"))
      (node (ref "R19") (pin "2") (pinfunction "2_2") (pintype "passive"))
      (node (ref "R23") (pin "1") (pinfunction "1_1") (pintype "passive"))
    )
    (net (code "35") (name "Net-(Q3-D)") (class "Default")
      (node (ref "Q3") (pin "3") (pinfunction "D_3") (pintype "passive"))
      (node (ref "Q4") (pin "4") (pinfunction "G1_4") (pintype "passive"))
      (node (ref "R26") (pin "2") (pinfunction "2_2") (pintype "passive"))
      (node (ref "R30") (pin "2") (pinfunction "2_2") (pintype "passive"))
    )
    (net (code "36") (name "Net-(Q4-D2a)") (class "Default")
      (node (ref "C26") (pin "2") (pinfunction "2_2") (pintype "passive"))
      (node (ref "C27") (pin "2") (pinfunction "2_2") (pintype "passive"))
      (node (ref "Q4") (pin "5") (pintype "passive"))
      (node (ref "Q4") (pin "6") (pintype "passive"))
      (node (ref "Q4") (pin "7") (pinfunction "D2a_7") (pintype "passive"))
      (node (ref "Q4") (pin "8") (pinfunction "D2b_8") (pintype "passive"))
      (node (ref "Q4") (pin "TAB") (pintype "passive"))
      (node (ref "Q5") (pin "5") (pintype "passive"))
      (node (ref "Q5") (pin "6") (pintype "passive"))
      (node (ref "Q5") (pin "7") (pinfunction "D2a_7") (pintype "passive"))
      (node (ref "Q5") (pin "8") (pinfunction "D2b_8") (pintype "passive"))
      (node (ref "Q5") (pin "TAB") (pintype "passive"))
      (node (ref "R32") (pin "2") (pinfunction "2_2") (pintype "passive"))
    )
    (net (code "37") (name "Net-(R36-I2)") (class "Default")
      (node (ref "L1") (pin "1") (pinfunction "1_1") (pintype "passive"))
      (node (ref "R36") (pin "2") (pinfunction "I2_2") (pintype "passive"))
    )
    (net (code "38") (name "Net-(U1-ACP)") (class "Default")
      (node (ref "R24") (pin "2") (pinfunction "2_2") (pintype "passive"))
      (node (ref "U1") (pin "31") (pinfunction "ACP_31") (pintype "passive"))
    )
    (net (code "39") (name "Net-(U1-CHG)") (class "Default")
      (node (ref "R22") (pin "2") (pinfunction "2_2") (pintype "passive"))
      (node (ref "U1") (pin "32") (pinfunction "CHG_32") (pintype "passive"))
    )
    (net (code "40") (name "Net-(U1-DSG)") (class "Default")
      (node (ref "R23") (pin "2") (pinfunction "2_2") (pintype "passive"))
      (node (ref "U1") (pin "30") (pinfunction "DSG_30") (pintype "passive"))
    )
    (net (code "41") (name "Net-(U1-PBI)") (class "Default")
      (node (ref "C18") (pin "2") (pinfunction "2_2") (pintype "passive"))
      (node (ref "U1") (pin "2") (pinfunction "PBI_2") (pintype "passive"))
    )
    (net (code "42") (name "Net-(U1-SRN)") (class "Default")
      (node (ref "C33") (pin "2") (pinfunction "2_2") (pintype "passive"))
      (node (ref "C34") (pin "1") (pinfunction "1_1") (pintype "passive"))
      (node (ref "R35") (pin "2") (pinfunction "2_2") (pintype "passive"))
      (node (ref "U1") (pin "7") (pinfunction "SRN_7") (pintype "passive"))
    )
    (net (code "43") (name "Net-(U1-SRP)") (class "Default")
      (node (ref "C33") (pin "1") (pinfunction "1_1") (pintype "passive"))
      (node (ref "C34") (pin "2") (pinfunction "2_2") (pintype "passive"))
      (node (ref "R33") (pin "2") (pinfunction "2_2") (pintype "passive"))
      (node (ref "U1") (pin "8") (pinfunction "SRP_8") (pintype "passive"))
    )
    (net (code "44") (name "Net-(U1-VCC)") (class "Default")
      (node (ref "C22") (pin "2") (pinfunction "2_2") (pintype "passive"))
      (node (ref "R32") (pin "1") (pinfunction "1_1") (pintype "passive"))
      (node (ref "U1") (pin "22") (pinfunction "VCC_22") (pintype "passive"))
    )
    (net (code "45") (name "VSYS") (class "Default")
      (node (ref "C16") (pin "1") (pinfunction "1_1") (pintype "passive"))
      (node (ref "C36") (pin "1") (pinfunction "1_1") (pintype "passive"))
      (node (ref "C37") (pin "1") (pinfunction "1_1") (pintype "passive"))
      (node (ref "C38") (pin "2") (pinfunction "2_2") (pintype "passive"))
      (node (ref "Q2") (pin "1") (pinfunction "S1_1") (pintype "passive"))
      (node (ref "Q2") (pin "2") (pintype "passive"))
      (node (ref "Q2") (pin "3") (pintype "passive"))
      (node (ref "R19") (pin "1") (pinfunction "1_1") (pintype "passive"))
      (node (ref "R36") (pin "1") (pinfunction "I1_1") (pintype "passive"))
      (node (ref "R37") (pin "1") (pinfunction "1_1") (pintype "passive"))
      (node (ref "T12") (pin "1") (pinfunction "1_1") (pintype "passive"))
      (node (ref "T16") (pin "2") (pinfunction "2_2") (pintype "passive"))
    )
    (net (code "46") (name "V_USB_HV") (class "Default")
      (node (ref "Q3") (pin "2") (pinfunction "S_2") (pintype "passive"))
      (node (ref "Q4") (pin "1") (pinfunction "S1_1") (pintype "passive"))
      (node (ref "Q4") (pin "2") (pintype "passive"))
      (node (ref "Q4") (pin "3") (pintype "passive"))
      (node (ref "R24") (pin "1") (pinfunction "1_1") (pintype "passive"))
      (node (ref "R26") (pin "1") (pinfunction "1_1") (pintype "passive"))
      (node (ref "R27") (pin "1") (pinfunction "1_1") (pintype "passive"))
      (node (ref "R28") (pin "1") (pinfunction "1_1") (pintype "passive"))
      (node (ref "T16") (pin "1") (pinfunction "1_1") (pintype "passive"))
    )
    (net (code "47") (name "unconnected-(J14-PadMNT)") (class "Default")
      (node (ref "J14") (pin "MNT") (pinfunction "MNT_MNT") (pintype "passive+no_connect"))
    )
    (net (code "48") (name "unconnected-(J15-PadMNT)") (class "Default")
      (node (ref "J15") (pin "MNT") (pinfunction "MNT_MNT") (pintype "passive+no_connect"))
    )
    (net (code "49") (name "unconnected-(U1-GPIO1-Pad15)") (class "Default")
      (node (ref "U1") (pin "15") (pinfunction "GPIO1_15") (pintype "passive+no_connect"))
    )
  )
)
